# Motor_V05.net
KiCad netlist of a schematic drawn in EAGLE
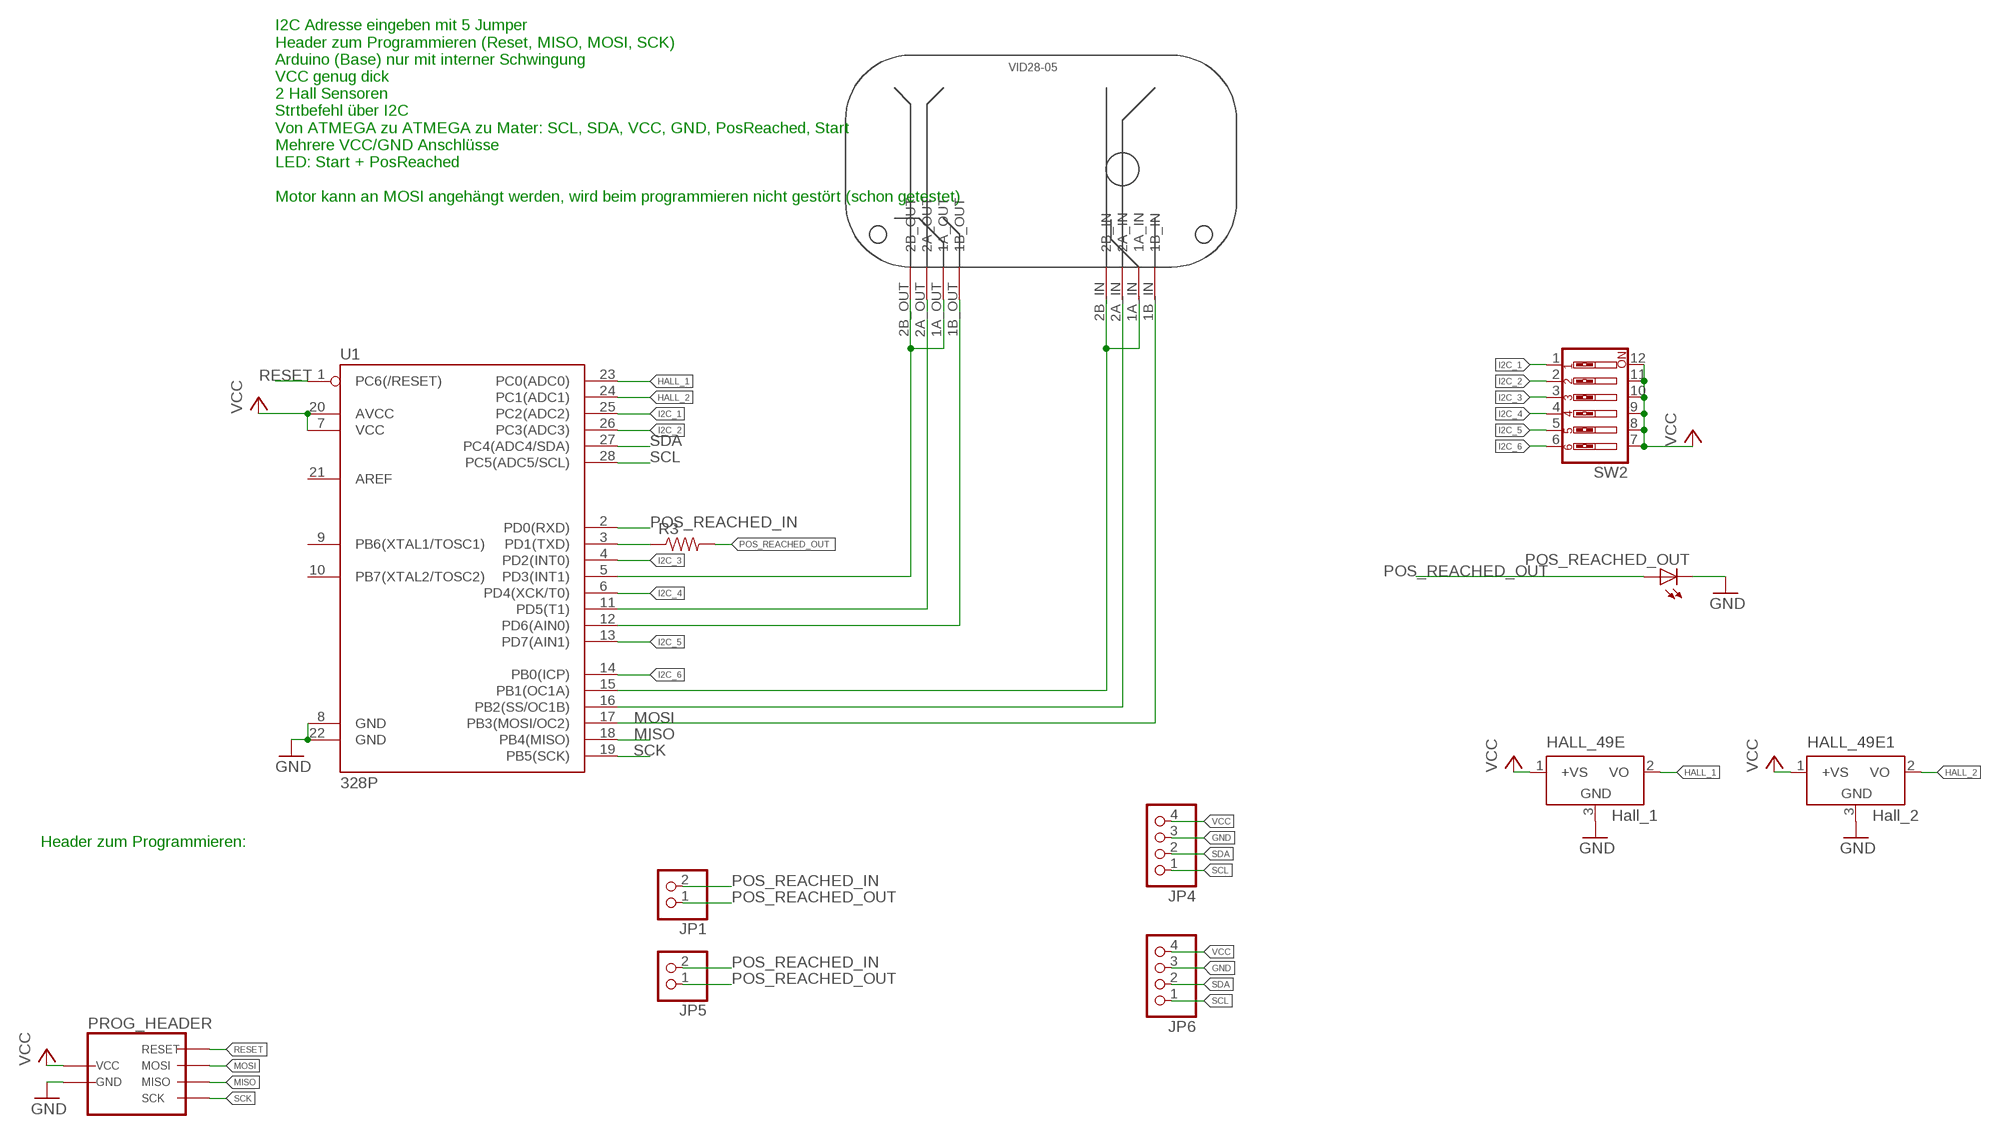
[diagram p0: schematic, sheet 1]

(export (version "E")
  (design (tool "Eeschema 10.0.6"))
  (components
    (comp (ref "HALL_49E")
      (value "Hall_1")
      (footprint "eagle-import:SOT23")
      (libsource (lib "eagle-import") (part "LM50"))
    )
    (comp (ref "HALL_49E1")
      (value "Hall_2")
      (footprint "eagle-import:SOT23")
      (libsource (lib "eagle-import") (part "LM50"))
    )
    (comp (ref "JP1")
      (value "PINHD-1X2")
      (footprint "eagle-import:1X02")
      (libsource (lib "eagle-import") (part "PINHD-1X2"))
    )
    (comp (ref "JP3")
      (value "ATMEGA_PROGRAM_HEADER")
      (footprint "eagle-import:ATMEGA_PROGRAM_HEADER")
      (libsource (lib "eagle-import") (part "ATMEGA_PROGRAM_HEADER"))
    )
    (comp (ref "JP4")
      (value "PINHD-1X4")
      (footprint "eagle-import:1X04")
      (libsource (lib "eagle-import") (part "PINHD-1X4"))
    )
    (comp (ref "JP5")
      (value "PINHD-1X2")
      (footprint "eagle-import:1X02")
      (libsource (lib "eagle-import") (part "PINHD-1X2"))
    )
    (comp (ref "JP6")
      (value "PINHD-1X4")
      (footprint "eagle-import:1X04")
      (libsource (lib "eagle-import") (part "PINHD-1X4"))
    )
    (comp (ref "POS_REACHED_OUT")
      (value "LED_ELD260")
      (footprint "eagle-import:LED_LD260")
      (libsource (lib "eagle-import") (part "LED_ELD260"))
    )
    (comp (ref "R3")
      (value "SPARKFUN_RESISTORAXIAL-0.3")
      (footprint "eagle-import:SPARKFUN_AXIAL-0.3")
      (libsource (lib "eagle-import") (part "SPARKFUN_RESISTORAXIAL-0.3"))
    )
    (comp (ref "SW2")
      (value "SW_DIP-6")
      (footprint "eagle-import:EDG-06")
      (libsource (lib "eagle-import") (part "SW_DIP-6"))
    )
    (comp (ref "U$4")
      (value "VID28-05")
      (footprint "eagle-import:VID28-05")
      (libsource (lib "eagle-import") (part "VID28-05"))
    )
    (comp (ref "U1")
      (value "328P")
      (footprint "eagle-import:DIP28")
      (libsource (lib "eagle-import") (part "ATMEGA328P_PDIP"))
    )
  )
  (nets
    (net (code "1") (name "/POS_REACHED_IN") (class "Default")
      (node (ref "JP1") (pin "2") (pinfunction "2_2") (pintype "passive"))
      (node (ref "JP5") (pin "2") (pinfunction "2_2") (pintype "passive"))
      (node (ref "U1") (pin "2") (pinfunction "PD0(RXD)_2") (pintype "bidirectional"))
    )
    (net (code "2") (name "GND") (class "Default")
      (node (ref "HALL_49E") (pin "3") (pinfunction "GND_3") (pintype "power_in"))
      (node (ref "HALL_49E1") (pin "3") (pinfunction "GND_3") (pintype "power_in"))
      (node (ref "JP3") (pin "GND") (pinfunction "GND_GND") (pintype "bidirectional"))
      (node (ref "JP4") (pin "3") (pinfunction "3_3") (pintype "passive"))
      (node (ref "JP6") (pin "3") (pinfunction "3_3") (pintype "passive"))
      (node (ref "POS_REACHED_OUT") (pin "K") (pinfunction "C_K") (pintype "passive"))
      (node (ref "U1") (pin "22") (pinfunction "GND_22") (pintype "bidirectional"))
      (node (ref "U1") (pin "8") (pinfunction "GND_8") (pintype "bidirectional"))
    )
    (net (code "3") (name "HALL_1") (class "Default")
      (node (ref "HALL_49E") (pin "2") (pinfunction "VO_2") (pintype "input"))
      (node (ref "U1") (pin "23") (pinfunction "PC0(ADC0)_23") (pintype "bidirectional"))
    )
    (net (code "4") (name "HALL_2") (class "Default")
      (node (ref "HALL_49E1") (pin "2") (pinfunction "VO_2") (pintype "input"))
      (node (ref "U1") (pin "24") (pinfunction "PC1(ADC1)_24") (pintype "bidirectional"))
    )
    (net (code "5") (name "I2C_1") (class "Default")
      (node (ref "SW2") (pin "1") (pinfunction "1_1") (pintype "passive"))
      (node (ref "U1") (pin "25") (pinfunction "PC2(ADC2)_25") (pintype "bidirectional"))
    )
    (net (code "6") (name "I2C_2") (class "Default")
      (node (ref "SW2") (pin "2") (pinfunction "2_2") (pintype "passive"))
      (node (ref "U1") (pin "26") (pinfunction "PC3(ADC3)_26") (pintype "bidirectional"))
    )
    (net (code "7") (name "I2C_3") (class "Default")
      (node (ref "SW2") (pin "3") (pinfunction "3_3") (pintype "passive"))
      (node (ref "U1") (pin "4") (pinfunction "PD2(INT0)_4") (pintype "bidirectional"))
    )
    (net (code "8") (name "I2C_4") (class "Default")
      (node (ref "SW2") (pin "4") (pinfunction "4_4") (pintype "passive"))
      (node (ref "U1") (pin "6") (pinfunction "PD4(XCK/T0)_6") (pintype "bidirectional"))
    )
    (net (code "9") (name "I2C_5") (class "Default")
      (node (ref "SW2") (pin "5") (pinfunction "5_5") (pintype "passive"))
      (node (ref "U1") (pin "13") (pinfunction "PD7(AIN1)_13") (pintype "bidirectional"))
    )
    (net (code "10") (name "I2C_6") (class "Default")
      (node (ref "SW2") (pin "6") (pinfunction "6_6") (pintype "passive"))
      (node (ref "U1") (pin "14") (pinfunction "PB0(ICP)_14") (pintype "bidirectional"))
    )
    (net (code "11") (name "MISO") (class "Default")
      (node (ref "JP3") (pin "MISO") (pinfunction "MISO_MISO") (pintype "bidirectional"))
      (node (ref "U1") (pin "18") (pinfunction "PB4(MISO)_18") (pintype "bidirectional"))
    )
    (net (code "12") (name "MOSI") (class "Default")
      (node (ref "JP3") (pin "MOSI") (pinfunction "MOSI_MOSI") (pintype "bidirectional"))
      (node (ref "U$4") (pin "1B_IN") (pinfunction "1B_IN_1B_IN") (pintype "bidirectional"))
      (node (ref "U1") (pin "17") (pinfunction "PB3(MOSI/OC2)_17") (pintype "bidirectional"))
    )
    (net (code "13") (name "Net-(R3-1)") (class "Default")
      (node (ref "R3") (pin "P$1") (pinfunction "1_P$1") (pintype "passive"))
      (node (ref "U1") (pin "3") (pinfunction "PD1(TXD)_3") (pintype "bidirectional"))
    )
    (net (code "14") (name "Net-(U1-PB1(OC1A))") (class "Default")
      (node (ref "U$4") (pin "1A_IN") (pinfunction "1A_IN_1A_IN") (pintype "bidirectional"))
      (node (ref "U$4") (pin "2B_IN") (pinfunction "2B_IN_2B_IN") (pintype "bidirectional"))
      (node (ref "U1") (pin "15") (pinfunction "PB1(OC1A)_15") (pintype "bidirectional"))
    )
    (net (code "15") (name "Net-(U1-PB2(SS{slash}OC1B))") (class "Default")
      (node (ref "U$4") (pin "2A_IN") (pinfunction "2A_IN_2A_IN") (pintype "bidirectional"))
      (node (ref "U1") (pin "16") (pinfunction "PB2(SS/OC1B)_16") (pintype "bidirectional"))
    )
    (net (code "16") (name "Net-(U1-PD3(INT1))") (class "Default")
      (node (ref "U$4") (pin "1A_OUT") (pinfunction "1A_OUT_1A_OUT") (pintype "bidirectional"))
      (node (ref "U$4") (pin "2B_OUT") (pinfunction "2B_OUT_2B_OUT") (pintype "bidirectional"))
      (node (ref "U1") (pin "5") (pinfunction "PD3(INT1)_5") (pintype "bidirectional"))
    )
    (net (code "17") (name "Net-(U1-PD5(T1))") (class "Default")
      (node (ref "U$4") (pin "2A_OUT") (pinfunction "2A_OUT_2A_OUT") (pintype "bidirectional"))
      (node (ref "U1") (pin "11") (pinfunction "PD5(T1)_11") (pintype "bidirectional"))
    )
    (net (code "18") (name "Net-(U1-PD6(AIN0))") (class "Default")
      (node (ref "U$4") (pin "1B_OUT") (pinfunction "1B_OUT_1B_OUT") (pintype "bidirectional"))
      (node (ref "U1") (pin "12") (pinfunction "PD6(AIN0)_12") (pintype "bidirectional"))
    )
    (net (code "19") (name "POS_REACHED_OUT") (class "Default")
      (node (ref "JP1") (pin "1") (pinfunction "1_1") (pintype "passive"))
      (node (ref "JP5") (pin "1") (pinfunction "1_1") (pintype "passive"))
      (node (ref "POS_REACHED_OUT") (pin "A") (pinfunction "A_A") (pintype "passive"))
      (node (ref "R3") (pin "P$2") (pinfunction "2_P$2") (pintype "passive"))
    )
    (net (code "20") (name "RESET") (class "Default")
      (node (ref "JP3") (pin "RESET") (pinfunction "RESET_RESET") (pintype "bidirectional"))
      (node (ref "U1") (pin "1") (pinfunction "PC6(/RESET)_1") (pintype "bidirectional"))
    )
    (net (code "21") (name "SCK") (class "Default")
      (node (ref "JP3") (pin "SCK") (pinfunction "SCK_SCK") (pintype "bidirectional"))
      (node (ref "U1") (pin "19") (pinfunction "PB5(SCK)_19") (pintype "bidirectional"))
    )
    (net (code "22") (name "SCL") (class "Default")
      (node (ref "JP4") (pin "1") (pinfunction "1_1") (pintype "passive"))
      (node (ref "JP6") (pin "1") (pinfunction "1_1") (pintype "passive"))
      (node (ref "U1") (pin "28") (pinfunction "PC5(ADC5/SCL)_28") (pintype "bidirectional"))
    )
    (net (code "23") (name "SDA") (class "Default")
      (node (ref "JP4") (pin "2") (pinfunction "2_2") (pintype "passive"))
      (node (ref "JP6") (pin "2") (pinfunction "2_2") (pintype "passive"))
      (node (ref "U1") (pin "27") (pinfunction "PC4(ADC4/SDA)_27") (pintype "bidirectional"))
    )
    (net (code "24") (name "VCC") (class "Default")
      (node (ref "HALL_49E") (pin "1") (pinfunction "+VS_1") (pintype "input"))
      (node (ref "HALL_49E1") (pin "1") (pinfunction "+VS_1") (pintype "input"))
      (node (ref "JP3") (pin "VCC") (pinfunction "VCC_VCC") (pintype "bidirectional"))
      (node (ref "JP4") (pin "4") (pinfunction "4_4") (pintype "passive"))
      (node (ref "JP6") (pin "4") (pinfunction "4_4") (pintype "passive"))
      (node (ref "SW2") (pin "10") (pinfunction "10_10") (pintype "passive"))
      (node (ref "SW2") (pin "11") (pinfunction "11_11") (pintype "passive"))
      (node (ref "SW2") (pin "12") (pinfunction "12_12") (pintype "passive"))
      (node (ref "SW2") (pin "7") (pinfunction "7_7") (pintype "passive"))
      (node (ref "SW2") (pin "8") (pinfunction "8_8") (pintype "passive"))
      (node (ref "SW2") (pin "9") (pinfunction "9_9") (pintype "passive"))
      (node (ref "U1") (pin "20") (pinfunction "AVCC_20") (pintype "bidirectional"))
      (node (ref "U1") (pin "7") (pinfunction "VCC_7") (pintype "bidirectional"))
    )
    (net (code "25") (name "unconnected-(U1-AREF-Pad21)") (class "Default")
      (node (ref "U1") (pin "21") (pinfunction "AREF_21") (pintype "bidirectional"))
    )
    (net (code "26") (name "unconnected-(U1-PB6(XTAL1{slash}TOSC1)-Pad9)") (class "Default")
      (node (ref "U1") (pin "9") (pinfunction "PB6(XTAL1/TOSC1)_9") (pintype "bidirectional"))
    )
    (net (code "27") (name "unconnected-(U1-PB7(XTAL2{slash}TOSC2)-Pad10)") (class "Default")
      (node (ref "U1") (pin "10") (pinfunction "PB7(XTAL2/TOSC2)_10") (pintype "bidirectional"))
    )
  )
)
